# Ethernet.net
KiCad netlist of a schematic drawn in Altium Designer
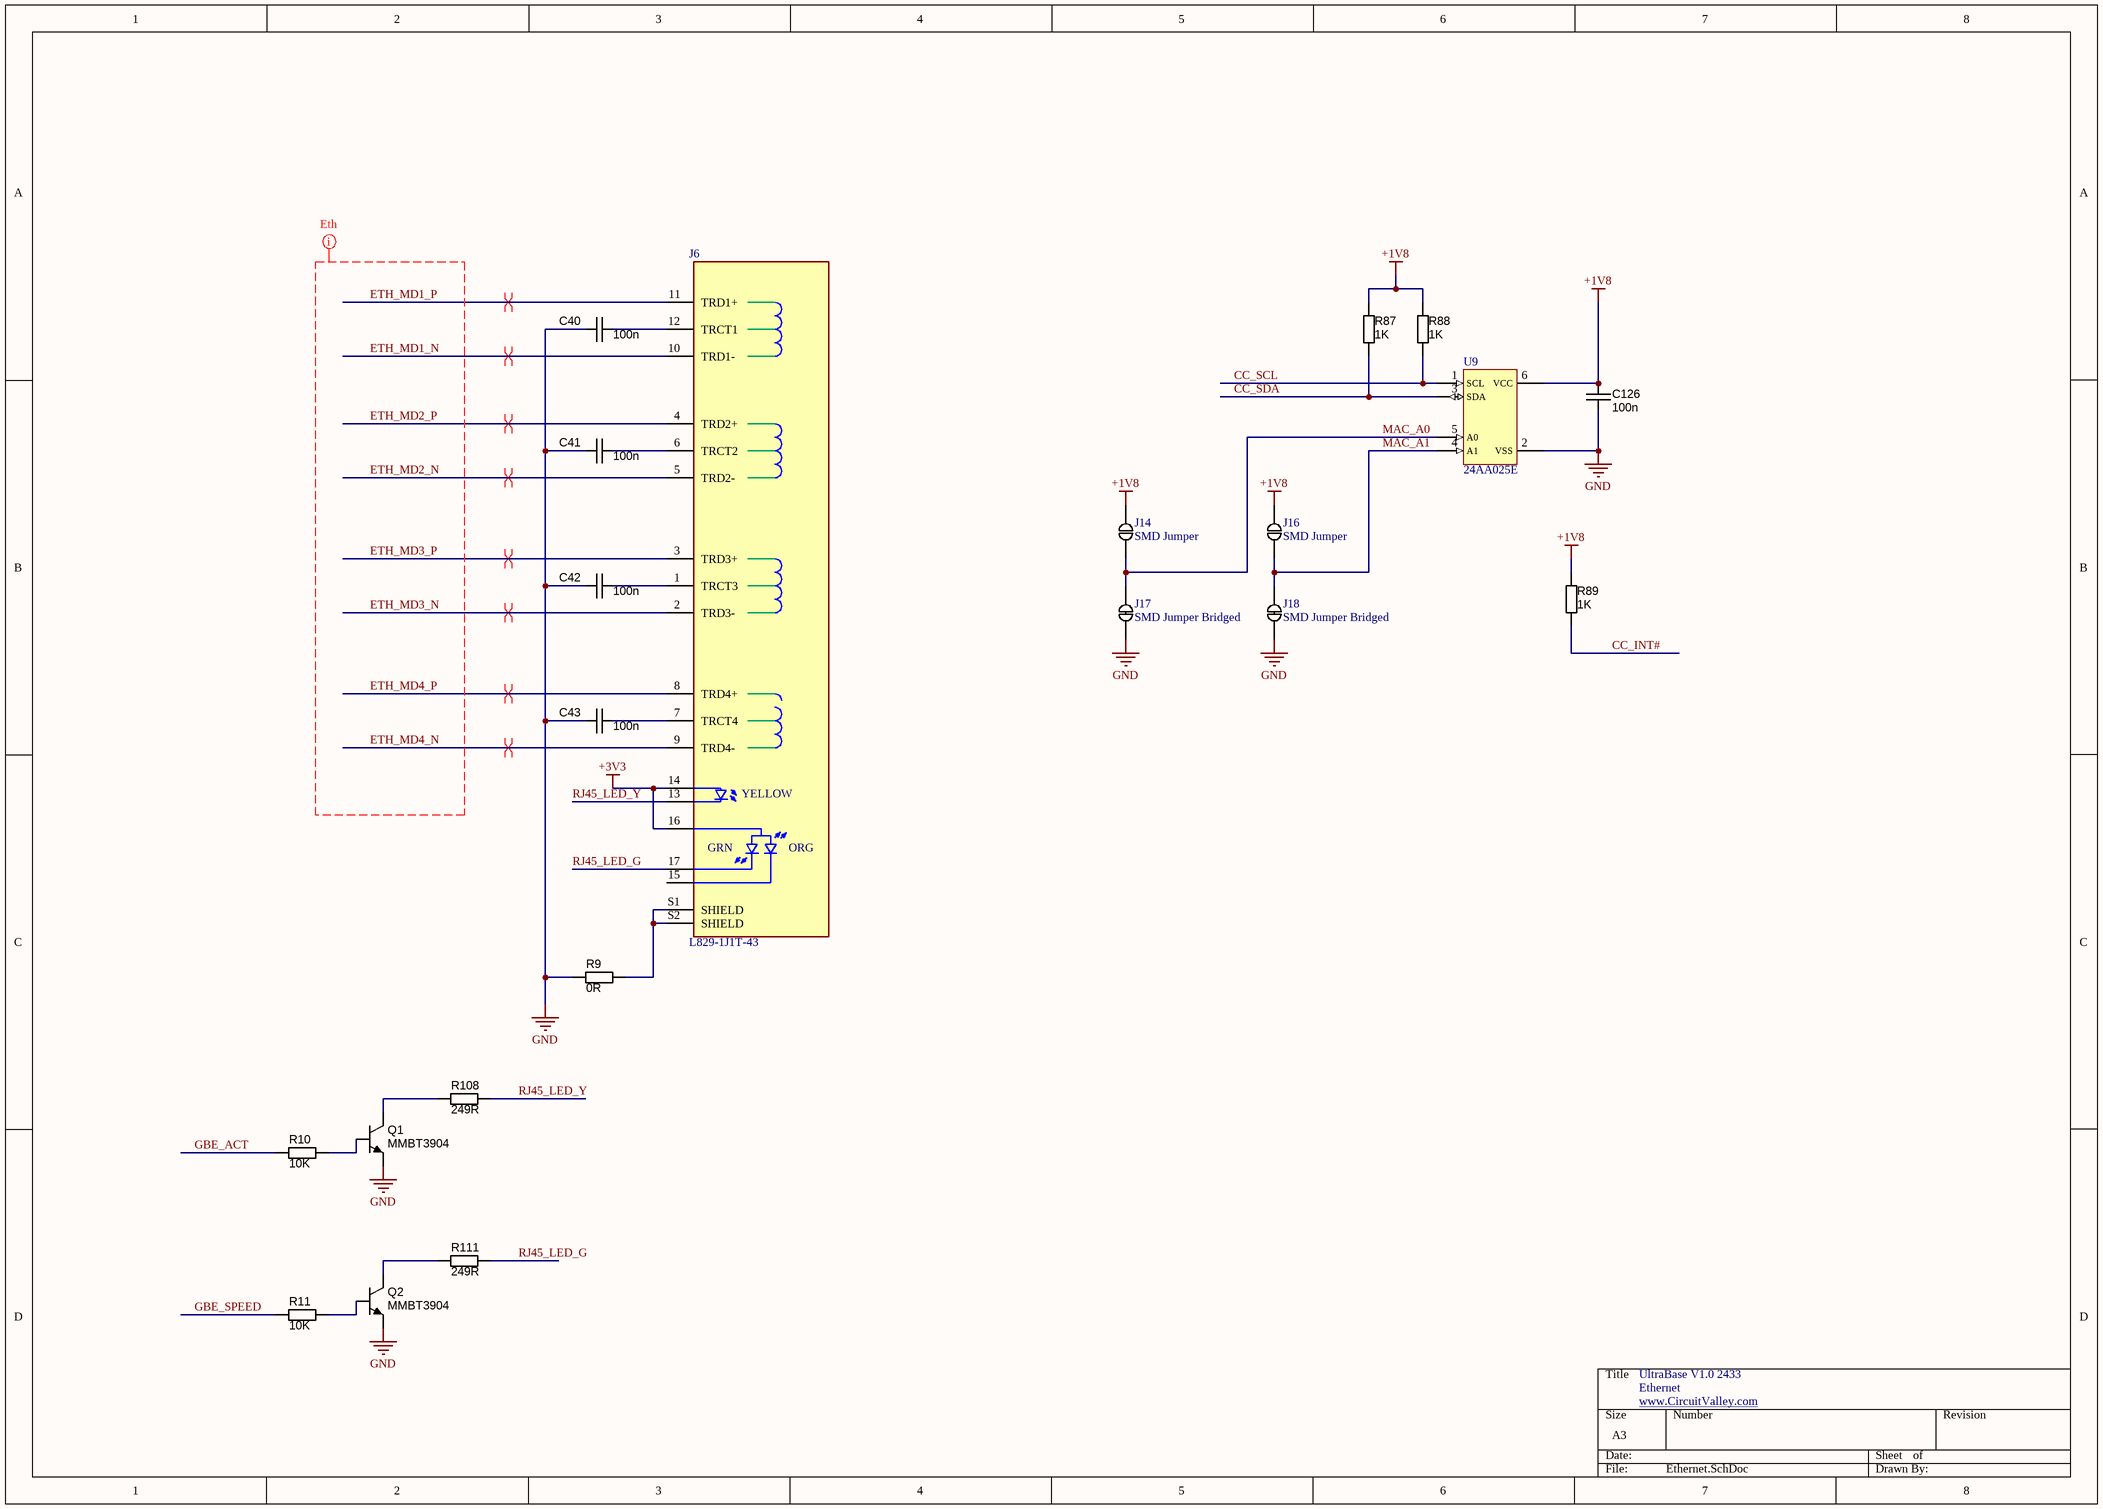
[diagram p0: Ethernet.SchDoc]

(export (version "E")
  (design (tool "Eeschema 10.0.6"))
  (components
    (comp (ref "C40")
      (value "100n")
      (footprint "CAPC1608N")
      (description "Capacitor SMD Cer 1nF 10% 100V X7R 0603")
      (fields (field (name "TOLERANCE") "±10%"))
      (libsource (lib "PBL - Capacitors") (part "CAPC_1n_0603_100V"))
    )
    (comp (ref "C41")
      (value "100n")
      (footprint "CAPC1608N")
      (description "Capacitor SMD Cer 1nF 10% 100V X7R 0603")
      (fields (field (name "TOLERANCE") "±10%"))
      (libsource (lib "PBL - Capacitors") (part "CAPC_1n_0603_100V"))
    )
    (comp (ref "C42")
      (value "100n")
      (footprint "CAPC1608N")
      (description "Capacitor SMD Cer 1nF 10% 100V X7R 0603")
      (fields (field (name "TOLERANCE") "±10%"))
      (libsource (lib "PBL - Capacitors") (part "CAPC_1n_0603_100V"))
    )
    (comp (ref "C43")
      (value "100n")
      (footprint "CAPC1608N")
      (description "Capacitor SMD Cer 1nF 10% 100V X7R 0603")
      (fields (field (name "TOLERANCE") "±10%"))
      (libsource (lib "PBL - Capacitors") (part "CAPC_1n_0603_100V"))
    )
    (comp (ref "C126")
      (value "100n")
      (footprint "CAPC1608N")
      (description "Capacitor SMD Cer 1nF 10% 100V X7R 0603")
      (fields (field (name "TOLERANCE") "±10%"))
      (libsource (lib "PBL - Capacitors") (part "CAPC_1n_0603_100V"))
    )
    (comp (ref "J6")
      (value "L829-1J1T-43")
      (footprint "L829-1J1T-43")
      (description "MagJack 1000BASE-T ¦ 1X1 ¦ 3w-OG/Y ¦ Tab Up ¦ Low Profile ¦ RoHS")
      (fields (field (name "MF") "Bel Fuse"))
      (libsource (lib "cvlib") (part "L829-1J1T-43"))
    )
    (comp (ref "J14")
      (value "SMD Jumper")
      (footprint "SMD_Jumper")
      (libsource (lib "cvlib") (part "SMD_Jumper"))
    )
    (comp (ref "J16")
      (value "SMD Jumper")
      (footprint "SMD_Jumper")
      (libsource (lib "cvlib") (part "SMD_Jumper"))
    )
    (comp (ref "J17")
      (value "SMD Jumper Bridged")
      (footprint "SMD_Jumper_bridge")
      (description "SMD Jumper")
      (libsource (lib "cvlib") (part "SMD_Jumper_Bridged"))
    )
    (comp (ref "J18")
      (value "SMD Jumper Bridged")
      (footprint "SMD_Jumper_bridge")
      (description "SMD Jumper")
      (libsource (lib "cvlib") (part "SMD_Jumper_Bridged"))
    )
    (comp (ref "Q1")
      (value "NPN_MMBT3904")
      (footprint "SOT23-3")
      (description "Transistor SMD NPN 40V 0.2A 350mW SOT-23")
      (fields (field (name "MANUFACTURER PART NUMBER 1") "MMBT3904"))
      (libsource (lib "PBL - Transistors") (part "NPN_MMBT3904"))
    )
    (comp (ref "Q2")
      (value "NPN_MMBT3904")
      (footprint "SOT23-3")
      (description "Transistor SMD NPN 40V 0.2A 350mW SOT-23")
      (fields (field (name "MANUFACTURER PART NUMBER 1") "MMBT3904"))
      (libsource (lib "PBL - Transistors") (part "NPN_MMBT3904"))
    )
    (comp (ref "R9")
      (value "0R")
      (footprint "RESC1608N")
      (description "Resistor, SMD chip")
      (fields (field (name "TOLERANCE") "±5%") (field (name "Comment") "RES_NL_0603"))
      (libsource (lib "PBL - Resistors") (part "RES_NL_0603"))
    )
    (comp (ref "R10")
      (value "10K")
      (footprint "RESC1608N")
      (description "Resistor, SMD chip")
      (fields (field (name "TOLERANCE") "±5%") (field (name "Comment") "RES_NL_0603"))
      (libsource (lib "PBL - Resistors") (part "RES_NL_0603"))
    )
    (comp (ref "R11")
      (value "10K")
      (footprint "RESC1608N")
      (description "Resistor, SMD chip")
      (fields (field (name "TOLERANCE") "±5%") (field (name "Comment") "RES_NL_0603"))
      (libsource (lib "PBL - Resistors") (part "RES_NL_0603"))
    )
    (comp (ref "R87")
      (value "1K")
      (footprint "RESC1608N")
      (description "Resistor, SMD chip")
      (fields (field (name "TOLERANCE") "±5%") (field (name "Comment") "RES_NL_0603"))
      (libsource (lib "") (part "RES_NL_0603_1"))
    )
    (comp (ref "R88")
      (value "1K")
      (footprint "RESC1608N")
      (description "Resistor, SMD chip")
      (fields (field (name "TOLERANCE") "±5%") (field (name "Comment") "RES_NL_0603"))
      (libsource (lib "") (part "RES_NL_0603_1"))
    )
    (comp (ref "R89")
      (value "1K")
      (footprint "RESC1608N")
      (description "Resistor, SMD chip")
      (fields (field (name "TOLERANCE") "±5%") (field (name "Comment") "RES_NL_0603"))
      (libsource (lib "") (part "RES_NL_0603_1"))
    )
    (comp (ref "R108")
      (value "249R")
      (footprint "RESC1608N")
      (description "Resistor, SMD chip")
      (fields (field (name "TOLERANCE") "±5%") (field (name "Comment") "RES_NL_0603"))
      (libsource (lib "PBL - Resistors") (part "RES_NL_0603"))
    )
    (comp (ref "R111")
      (value "249R")
      (footprint "RESC1608N")
      (description "Resistor, SMD chip")
      (fields (field (name "TOLERANCE") "±5%") (field (name "Comment") "RES_NL_0603"))
      (libsource (lib "PBL - Resistors") (part "RES_NL_0603"))
    )
    (comp (ref "U9")
      (value "24AA025E")
      (footprint "SOT23-6")
      (description "MAC EEPROM")
      (libsource (lib "cvlib") (part "24AA025E"))
    )
  )
  (nets
    (net (code "1") (name "+1V8") (class "Default")
      (node (ref "C126") (pin "2") (pintype "passive"))
      (node (ref "J14") (pin "2") (pinfunction "2_2") (pintype "passive"))
      (node (ref "J16") (pin "2") (pinfunction "2_2") (pintype "passive"))
      (node (ref "R87") (pin "2") (pinfunction "2_2") (pintype "passive"))
      (node (ref "R88") (pin "2") (pinfunction "2_2") (pintype "passive"))
      (node (ref "R89") (pin "2") (pinfunction "2_2") (pintype "passive"))
      (node (ref "U9") (pin "6") (pinfunction "VCC_6") (pintype "power_in"))
    )
    (net (code "2") (name "+3V3") (class "Default")
      (node (ref "J6") (pin "14") (pinfunction "YA_1_14") (pintype "passive"))
      (node (ref "J6") (pin "16") (pinfunction "CA_16") (pintype "passive"))
    )
    (net (code "3") (name "/CC_INT#") (class "Default")
      (node (ref "R89") (pin "1") (pinfunction "1_1") (pintype "passive"))
    )
    (net (code "4") (name "/CC_SCL") (class "Default")
      (node (ref "R88") (pin "1") (pinfunction "1_1") (pintype "passive"))
      (node (ref "U9") (pin "1") (pinfunction "SCL_1") (pintype "input"))
    )
    (net (code "5") (name "/CC_SDA") (class "Default")
      (node (ref "R87") (pin "1") (pinfunction "1_1") (pintype "passive"))
      (node (ref "U9") (pin "3") (pinfunction "SDA_3") (pintype "bidirectional"))
    )
    (net (code "6") (name "/ETH_MD1_N") (class "Default")
      (node (ref "J6") (pin "10") (pinfunction "TRD1-_10") (pintype "passive"))
    )
    (net (code "7") (name "/ETH_MD1_P") (class "Default")
      (node (ref "J6") (pin "11") (pinfunction "TRD1+_11") (pintype "passive"))
    )
    (net (code "8") (name "/ETH_MD2_N") (class "Default")
      (node (ref "J6") (pin "5") (pinfunction "TRD2-_5") (pintype "passive"))
    )
    (net (code "9") (name "/ETH_MD2_P") (class "Default")
      (node (ref "J6") (pin "4") (pinfunction "TRD2+_4") (pintype "passive"))
    )
    (net (code "10") (name "/ETH_MD3_N") (class "Default")
      (node (ref "J6") (pin "2") (pinfunction "TRD3-_2") (pintype "passive"))
    )
    (net (code "11") (name "/ETH_MD3_P") (class "Default")
      (node (ref "J6") (pin "3") (pinfunction "TRD3+_3") (pintype "passive"))
    )
    (net (code "12") (name "/ETH_MD4_N") (class "Default")
      (node (ref "J6") (pin "9") (pinfunction "TRD4-_9") (pintype "passive"))
    )
    (net (code "13") (name "/ETH_MD4_P") (class "Default")
      (node (ref "J6") (pin "8") (pinfunction "TRD4+_8") (pintype "passive"))
    )
    (net (code "14") (name "/GBE_ACT") (class "Default")
      (node (ref "R10") (pin "1") (pinfunction "1_1") (pintype "passive"))
    )
    (net (code "15") (name "/GBE_SPEED") (class "Default")
      (node (ref "R11") (pin "1") (pinfunction "1_1") (pintype "passive"))
    )
    (net (code "16") (name "/MAC_A0") (class "Default")
      (node (ref "J14") (pin "1") (pinfunction "1_1") (pintype "passive"))
      (node (ref "J17") (pin "2") (pinfunction "2_2") (pintype "passive"))
      (node (ref "U9") (pin "5") (pinfunction "A0_5") (pintype "input"))
    )
    (net (code "17") (name "/MAC_A1") (class "Default")
      (node (ref "J16") (pin "1") (pinfunction "1_1") (pintype "passive"))
      (node (ref "J18") (pin "2") (pinfunction "2_2") (pintype "passive"))
      (node (ref "U9") (pin "4") (pinfunction "A1_4") (pintype "input"))
    )
    (net (code "18") (name "/RJ45_LED_G") (class "Default")
      (node (ref "J6") (pin "17") (pinfunction "GK_1_17") (pintype "passive"))
      (node (ref "R111") (pin "2") (pinfunction "2_2") (pintype "passive"))
    )
    (net (code "19") (name "/RJ45_LED_Y") (class "Default")
      (node (ref "J6") (pin "13") (pinfunction "YK_1_13") (pintype "passive"))
      (node (ref "R108") (pin "2") (pinfunction "2_2") (pintype "passive"))
    )
    (net (code "20") (name "GND") (class "Default")
      (node (ref "C126") (pin "1") (pintype "passive"))
      (node (ref "C40") (pin "1") (pintype "passive"))
      (node (ref "C41") (pin "1") (pintype "passive"))
      (node (ref "C42") (pin "1") (pintype "passive"))
      (node (ref "C43") (pin "1") (pintype "passive"))
      (node (ref "J17") (pin "1") (pinfunction "1_1") (pintype "passive"))
      (node (ref "J18") (pin "1") (pinfunction "1_1") (pintype "passive"))
      (node (ref "Q1") (pin "2") (pinfunction "E_2") (pintype "passive"))
      (node (ref "Q2") (pin "2") (pinfunction "E_2") (pintype "passive"))
      (node (ref "R9") (pin "1") (pinfunction "1_1") (pintype "passive"))
      (node (ref "U9") (pin "2") (pinfunction "VSS_2") (pintype "passive"))
    )
    (net (code "21") (name "Net-(J6-SHIELD-PadS1)") (class "Default")
      (node (ref "J6") (pin "S1") (pinfunction "SHIELD_S1") (pintype "passive"))
      (node (ref "J6") (pin "S2") (pinfunction "SHIELD_S2") (pintype "passive"))
      (node (ref "R9") (pin "2") (pinfunction "2_2") (pintype "passive"))
    )
    (net (code "22") (name "Net-(J6-TRCT1)") (class "Default")
      (node (ref "C40") (pin "2") (pintype "passive"))
      (node (ref "J6") (pin "12") (pinfunction "TRCT1_12") (pintype "passive"))
    )
    (net (code "23") (name "Net-(J6-TRCT2)") (class "Default")
      (node (ref "C41") (pin "2") (pintype "passive"))
      (node (ref "J6") (pin "6") (pinfunction "TRCT2_6") (pintype "passive"))
    )
    (net (code "24") (name "Net-(J6-TRCT3)") (class "Default")
      (node (ref "C42") (pin "2") (pintype "passive"))
      (node (ref "J6") (pin "1") (pinfunction "TRCT3_1") (pintype "passive"))
    )
    (net (code "25") (name "Net-(J6-TRCT4)") (class "Default")
      (node (ref "C43") (pin "2") (pintype "passive"))
      (node (ref "J6") (pin "7") (pinfunction "TRCT4_7") (pintype "passive"))
    )
    (net (code "26") (name "Net-(Q1-B)") (class "Default")
      (node (ref "Q1") (pin "1") (pinfunction "B_1") (pintype "passive"))
      (node (ref "R10") (pin "2") (pinfunction "2_2") (pintype "passive"))
    )
    (net (code "27") (name "Net-(Q1-C)") (class "Default")
      (node (ref "Q1") (pin "3") (pinfunction "C_3") (pintype "passive"))
      (node (ref "R108") (pin "1") (pinfunction "1_1") (pintype "passive"))
    )
    (net (code "28") (name "Net-(Q2-B)") (class "Default")
      (node (ref "Q2") (pin "1") (pinfunction "B_1") (pintype "passive"))
      (node (ref "R11") (pin "2") (pinfunction "2_2") (pintype "passive"))
    )
    (net (code "29") (name "Net-(Q2-C)") (class "Default")
      (node (ref "Q2") (pin "3") (pinfunction "C_3") (pintype "passive"))
      (node (ref "R111") (pin "1") (pinfunction "1_1") (pintype "passive"))
    )
    (net (code "30") (name "unconnected-(J6-OK_1-Pad15)") (class "Default")
      (node (ref "J6") (pin "15") (pinfunction "OK_1_15") (pintype "passive"))
    )
  )
)
